# try.net
KiCad netlist of a schematic drawn in EAGLE
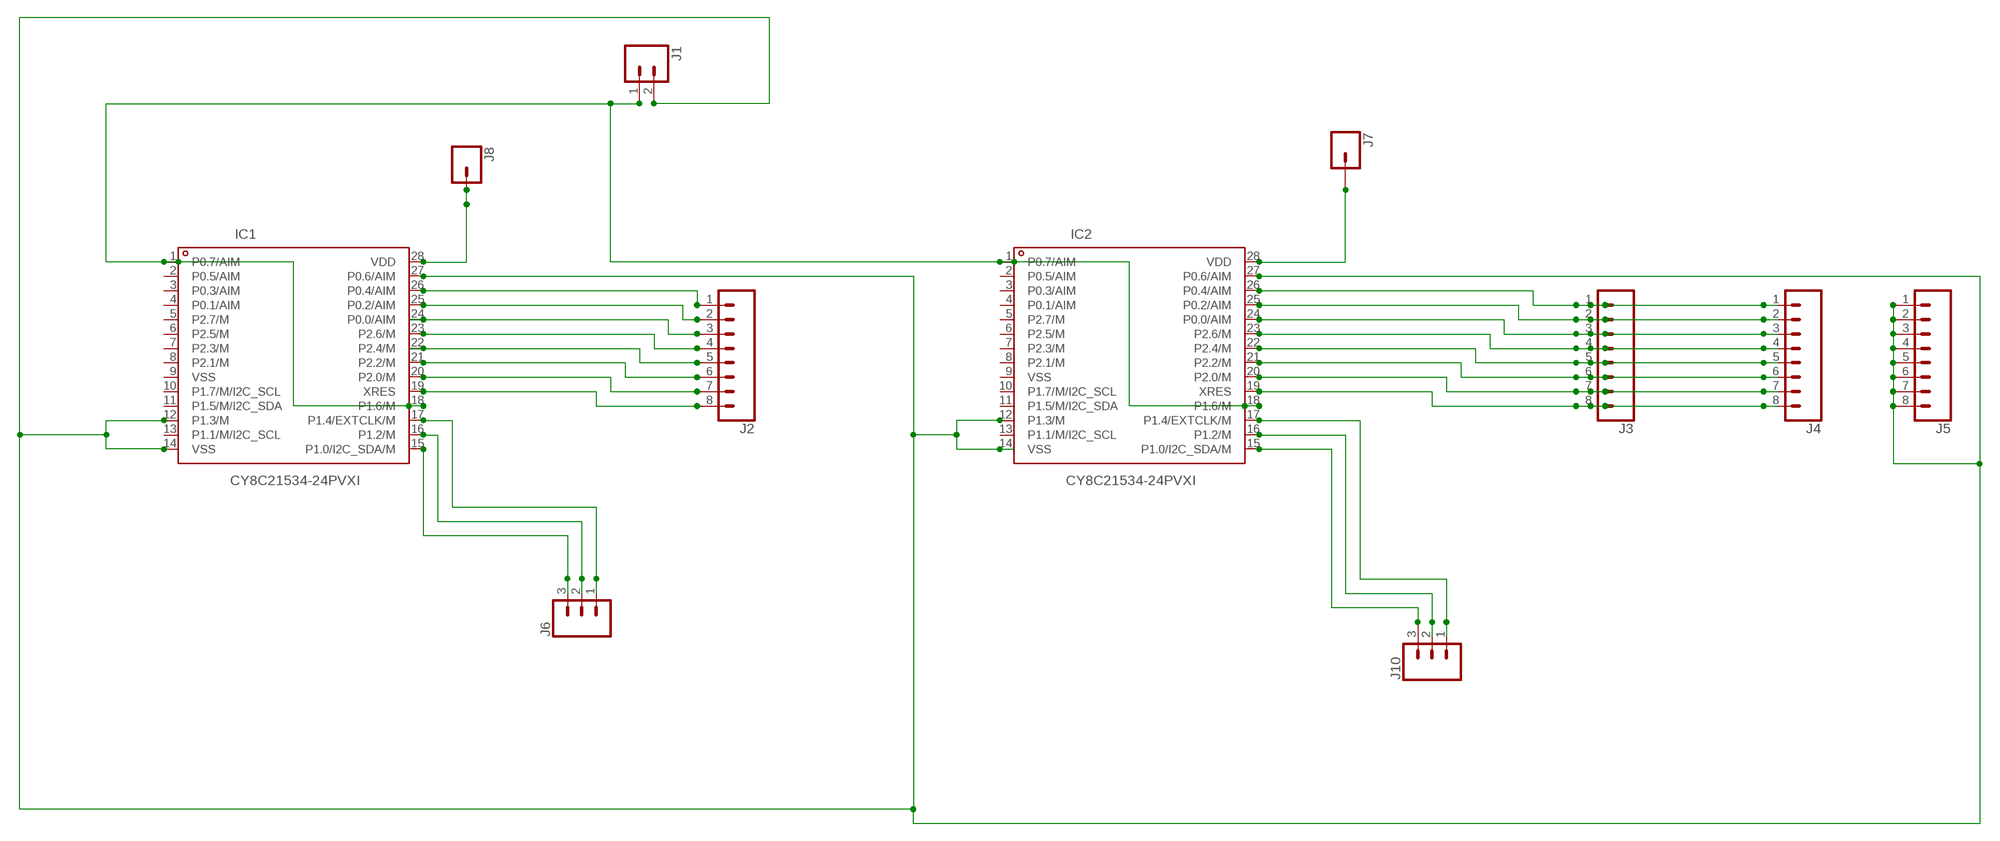
[diagram p0: schematic, sheet 1]

(export (version "E")
  (design (tool "Eeschema 10.0.6"))
  (components
    (comp (ref "IC1")
      (value "CY8C21534-24PVXI")
      (footprint "eagle-import:SSOP28")
      (libsource (lib "eagle-import") (part "CY8C21534-24PVXI"))
    )
    (comp (ref "IC2")
      (value "CY8C21534-24PVXI")
      (footprint "eagle-import:SSOP28")
      (libsource (lib "eagle-import") (part "CY8C21534-24PVXI"))
    )
    (comp (ref "J1")
      (value "CONN_02PTH3")
      (footprint "eagle-import:1X02_LONGPADS")
      (libsource (lib "eagle-import") (part "CONN_02PTH3"))
    )
    (comp (ref "J2")
      (value "CONN_08LONGPADS")
      (footprint "eagle-import:1X08_LONGPADS")
      (libsource (lib "eagle-import") (part "CONN_08LONGPADS"))
    )
    (comp (ref "J3")
      (value "CONN_08LONGPADS")
      (footprint "eagle-import:1X08_LONGPADS")
      (libsource (lib "eagle-import") (part "CONN_08LONGPADS"))
    )
    (comp (ref "J4")
      (value "CONN_08LONGPADS")
      (footprint "eagle-import:1X08_LONGPADS")
      (libsource (lib "eagle-import") (part "CONN_08LONGPADS"))
    )
    (comp (ref "J5")
      (value "CONN_08LONGPADS")
      (footprint "eagle-import:1X08_LONGPADS")
      (libsource (lib "eagle-import") (part "CONN_08LONGPADS"))
    )
    (comp (ref "J6")
      (value "CONN_03LONGPADS")
      (footprint "eagle-import:1X03_LONGPADS")
      (libsource (lib "eagle-import") (part "CONN_03LONGPADS"))
    )
    (comp (ref "J7")
      (value "CONN_01PTH_LONGPAD")
      (footprint "eagle-import:1X01_LONGPAD")
      (libsource (lib "eagle-import") (part "CONN_01PTH_LONGPAD"))
    )
    (comp (ref "J8")
      (value "CONN_01PTH_LONGPAD")
      (footprint "eagle-import:1X01_LONGPAD")
      (libsource (lib "eagle-import") (part "CONN_01PTH_LONGPAD"))
    )
    (comp (ref "J10")
      (value "CONN_03LONGPADS")
      (footprint "eagle-import:1X03_LONGPADS")
      (libsource (lib "eagle-import") (part "CONN_03LONGPADS"))
    )
  )
  (nets
    (net (code "1") (name "Net-(IC1-P0.0{slash}AIM)") (class "Default")
      (node (ref "IC1") (pin "24") (pinfunction "P0.0/AIM_24") (pintype "bidirectional"))
      (node (ref "J2") (pin "3") (pinfunction "3_3") (pintype "passive"))
    )
    (net (code "2") (name "Net-(IC1-P0.2{slash}AIM)") (class "Default")
      (node (ref "IC1") (pin "25") (pinfunction "P0.2/AIM_25") (pintype "bidirectional"))
      (node (ref "J2") (pin "2") (pinfunction "2_2") (pintype "passive"))
    )
    (net (code "3") (name "Net-(IC1-P0.4{slash}AIM)") (class "Default")
      (node (ref "IC1") (pin "26") (pinfunction "P0.4/AIM_26") (pintype "bidirectional"))
      (node (ref "J2") (pin "1") (pinfunction "1_1") (pintype "passive"))
    )
    (net (code "4") (name "Net-(IC1-P0.6{slash}AIM)") (class "Default")
      (node (ref "IC1") (pin "12") (pinfunction "P1.3/M_12") (pintype "bidirectional"))
      (node (ref "IC1") (pin "14") (pinfunction "VSS_14") (pintype "bidirectional"))
      (node (ref "IC1") (pin "27") (pinfunction "P0.6/AIM_27") (pintype "bidirectional"))
      (node (ref "IC2") (pin "12") (pinfunction "P1.3/M_12") (pintype "bidirectional"))
      (node (ref "IC2") (pin "14") (pinfunction "VSS_14") (pintype "bidirectional"))
      (node (ref "IC2") (pin "27") (pinfunction "P0.6/AIM_27") (pintype "bidirectional"))
      (node (ref "J1") (pin "2") (pinfunction "2_2") (pintype "passive"))
      (node (ref "J5") (pin "1") (pinfunction "1_1") (pintype "passive"))
      (node (ref "J5") (pin "2") (pinfunction "2_2") (pintype "passive"))
      (node (ref "J5") (pin "3") (pinfunction "3_3") (pintype "passive"))
      (node (ref "J5") (pin "4") (pinfunction "4_4") (pintype "passive"))
      (node (ref "J5") (pin "5") (pinfunction "5_5") (pintype "passive"))
      (node (ref "J5") (pin "6") (pinfunction "6_6") (pintype "passive"))
      (node (ref "J5") (pin "7") (pinfunction "7_7") (pintype "passive"))
      (node (ref "J5") (pin "8") (pinfunction "8_8") (pintype "passive"))
    )
    (net (code "5") (name "Net-(IC1-P0.7{slash}AIM)") (class "Default")
      (node (ref "IC1") (pin "1") (pinfunction "P0.7/AIM_1") (pintype "bidirectional"))
      (node (ref "IC1") (pin "18") (pinfunction "P1.6/M_18") (pintype "bidirectional"))
      (node (ref "IC2") (pin "1") (pinfunction "P0.7/AIM_1") (pintype "bidirectional"))
      (node (ref "IC2") (pin "18") (pinfunction "P1.6/M_18") (pintype "bidirectional"))
      (node (ref "J1") (pin "1") (pinfunction "1_1") (pintype "passive"))
    )
    (net (code "6") (name "Net-(IC1-P1.0{slash}I2C_SDA{slash}M)") (class "Default")
      (node (ref "IC1") (pin "15") (pinfunction "P1.0/I2C_SDA/M_15") (pintype "bidirectional"))
      (node (ref "J6") (pin "3") (pinfunction "3_3") (pintype "passive"))
    )
    (net (code "7") (name "Net-(IC1-P1.2{slash}M)") (class "Default")
      (node (ref "IC1") (pin "16") (pinfunction "P1.2/M_16") (pintype "bidirectional"))
      (node (ref "J6") (pin "2") (pinfunction "2_2") (pintype "passive"))
    )
    (net (code "8") (name "Net-(IC1-P1.4{slash}EXTCLK{slash}M)") (class "Default")
      (node (ref "IC1") (pin "17") (pinfunction "P1.4/EXTCLK/M_17") (pintype "bidirectional"))
      (node (ref "J6") (pin "1") (pinfunction "1_1") (pintype "passive"))
    )
    (net (code "9") (name "Net-(IC1-P2.0{slash}M)") (class "Default")
      (node (ref "IC1") (pin "20") (pinfunction "P2.0/M_20") (pintype "bidirectional"))
      (node (ref "J2") (pin "7") (pinfunction "7_7") (pintype "passive"))
    )
    (net (code "10") (name "Net-(IC1-P2.2{slash}M)") (class "Default")
      (node (ref "IC1") (pin "21") (pinfunction "P2.2/M_21") (pintype "bidirectional"))
      (node (ref "J2") (pin "6") (pinfunction "6_6") (pintype "passive"))
    )
    (net (code "11") (name "Net-(IC1-P2.4{slash}M)") (class "Default")
      (node (ref "IC1") (pin "22") (pinfunction "P2.4/M_22") (pintype "bidirectional"))
      (node (ref "J2") (pin "5") (pinfunction "5_5") (pintype "passive"))
    )
    (net (code "12") (name "Net-(IC1-P2.6{slash}M)") (class "Default")
      (node (ref "IC1") (pin "23") (pinfunction "P2.6/M_23") (pintype "bidirectional"))
      (node (ref "J2") (pin "4") (pinfunction "4_4") (pintype "passive"))
    )
    (net (code "13") (name "Net-(IC1-VDD)") (class "Default")
      (node (ref "IC1") (pin "28") (pinfunction "VDD_28") (pintype "bidirectional"))
      (node (ref "J8") (pin "1") (pinfunction "1_1") (pintype "passive"))
    )
    (net (code "14") (name "Net-(IC1-XRES)") (class "Default")
      (node (ref "IC1") (pin "19") (pinfunction "XRES_19") (pintype "bidirectional"))
      (node (ref "J2") (pin "8") (pinfunction "8_8") (pintype "passive"))
    )
    (net (code "15") (name "Net-(IC2-P0.0{slash}AIM)") (class "Default")
      (node (ref "IC2") (pin "24") (pinfunction "P0.0/AIM_24") (pintype "bidirectional"))
      (node (ref "J3") (pin "3") (pinfunction "3_3") (pintype "passive"))
      (node (ref "J4") (pin "3") (pinfunction "3_3") (pintype "passive"))
    )
    (net (code "16") (name "Net-(IC2-P0.2{slash}AIM)") (class "Default")
      (node (ref "IC2") (pin "25") (pinfunction "P0.2/AIM_25") (pintype "bidirectional"))
      (node (ref "J3") (pin "2") (pinfunction "2_2") (pintype "passive"))
      (node (ref "J4") (pin "2") (pinfunction "2_2") (pintype "passive"))
    )
    (net (code "17") (name "Net-(IC2-P0.4{slash}AIM)") (class "Default")
      (node (ref "IC2") (pin "26") (pinfunction "P0.4/AIM_26") (pintype "bidirectional"))
      (node (ref "J3") (pin "1") (pinfunction "1_1") (pintype "passive"))
      (node (ref "J4") (pin "1") (pinfunction "1_1") (pintype "passive"))
    )
    (net (code "18") (name "Net-(IC2-P1.0{slash}I2C_SDA{slash}M)") (class "Default")
      (node (ref "IC2") (pin "15") (pinfunction "P1.0/I2C_SDA/M_15") (pintype "bidirectional"))
      (node (ref "J10") (pin "3") (pinfunction "3_3") (pintype "passive"))
    )
    (net (code "19") (name "Net-(IC2-P1.2{slash}M)") (class "Default")
      (node (ref "IC2") (pin "16") (pinfunction "P1.2/M_16") (pintype "bidirectional"))
      (node (ref "J10") (pin "2") (pinfunction "2_2") (pintype "passive"))
    )
    (net (code "20") (name "Net-(IC2-P1.4{slash}EXTCLK{slash}M)") (class "Default")
      (node (ref "IC2") (pin "17") (pinfunction "P1.4/EXTCLK/M_17") (pintype "bidirectional"))
      (node (ref "J10") (pin "1") (pinfunction "1_1") (pintype "passive"))
    )
    (net (code "21") (name "Net-(IC2-P2.0{slash}M)") (class "Default")
      (node (ref "IC2") (pin "20") (pinfunction "P2.0/M_20") (pintype "bidirectional"))
      (node (ref "J3") (pin "7") (pinfunction "7_7") (pintype "passive"))
      (node (ref "J4") (pin "7") (pinfunction "7_7") (pintype "passive"))
    )
    (net (code "22") (name "Net-(IC2-P2.2{slash}M)") (class "Default")
      (node (ref "IC2") (pin "21") (pinfunction "P2.2/M_21") (pintype "bidirectional"))
      (node (ref "J3") (pin "6") (pinfunction "6_6") (pintype "passive"))
      (node (ref "J4") (pin "6") (pinfunction "6_6") (pintype "passive"))
    )
    (net (code "23") (name "Net-(IC2-P2.4{slash}M)") (class "Default")
      (node (ref "IC2") (pin "22") (pinfunction "P2.4/M_22") (pintype "bidirectional"))
      (node (ref "J3") (pin "5") (pinfunction "5_5") (pintype "passive"))
      (node (ref "J4") (pin "5") (pinfunction "5_5") (pintype "passive"))
    )
    (net (code "24") (name "Net-(IC2-P2.6{slash}M)") (class "Default")
      (node (ref "IC2") (pin "23") (pinfunction "P2.6/M_23") (pintype "bidirectional"))
      (node (ref "J3") (pin "4") (pinfunction "4_4") (pintype "passive"))
      (node (ref "J4") (pin "4") (pinfunction "4_4") (pintype "passive"))
    )
    (net (code "25") (name "Net-(IC2-VDD)") (class "Default")
      (node (ref "IC2") (pin "28") (pinfunction "VDD_28") (pintype "bidirectional"))
      (node (ref "J7") (pin "1") (pinfunction "1_1") (pintype "passive"))
    )
    (net (code "26") (name "Net-(IC2-XRES)") (class "Default")
      (node (ref "IC2") (pin "19") (pinfunction "XRES_19") (pintype "bidirectional"))
      (node (ref "J3") (pin "8") (pinfunction "8_8") (pintype "passive"))
      (node (ref "J4") (pin "8") (pinfunction "8_8") (pintype "passive"))
    )
    (net (code "27") (name "unconnected-(IC1-P0.1{slash}AIM-Pad4)") (class "Default")
      (node (ref "IC1") (pin "4") (pinfunction "P0.1/AIM_4") (pintype "bidirectional"))
    )
    (net (code "28") (name "unconnected-(IC1-P0.3{slash}AIM-Pad3)") (class "Default")
      (node (ref "IC1") (pin "3") (pinfunction "P0.3/AIM_3") (pintype "bidirectional"))
    )
    (net (code "29") (name "unconnected-(IC1-P0.5{slash}AIM-Pad2)") (class "Default")
      (node (ref "IC1") (pin "2") (pinfunction "P0.5/AIM_2") (pintype "bidirectional"))
    )
    (net (code "30") (name "unconnected-(IC1-P1.1{slash}M{slash}I2C_SCL-Pad13)") (class "Default")
      (node (ref "IC1") (pin "13") (pinfunction "P1.1/M/I2C_SCL_13") (pintype "bidirectional"))
    )
    (net (code "31") (name "unconnected-(IC1-P1.5{slash}M{slash}I2C_SDA-Pad11)") (class "Default")
      (node (ref "IC1") (pin "11") (pinfunction "P1.5/M/I2C_SDA_11") (pintype "bidirectional"))
    )
    (net (code "32") (name "unconnected-(IC1-P1.7{slash}M{slash}I2C_SCL-Pad10)") (class "Default")
      (node (ref "IC1") (pin "10") (pinfunction "P1.7/M/I2C_SCL_10") (pintype "bidirectional"))
    )
    (net (code "33") (name "unconnected-(IC1-P2.1{slash}M-Pad8)") (class "Default")
      (node (ref "IC1") (pin "8") (pinfunction "P2.1/M_8") (pintype "bidirectional"))
    )
    (net (code "34") (name "unconnected-(IC1-P2.3{slash}M-Pad7)") (class "Default")
      (node (ref "IC1") (pin "7") (pinfunction "P2.3/M_7") (pintype "bidirectional"))
    )
    (net (code "35") (name "unconnected-(IC1-P2.5{slash}M-Pad6)") (class "Default")
      (node (ref "IC1") (pin "6") (pinfunction "P2.5/M_6") (pintype "bidirectional"))
    )
    (net (code "36") (name "unconnected-(IC1-P2.7{slash}M-Pad5)") (class "Default")
      (node (ref "IC1") (pin "5") (pinfunction "P2.7/M_5") (pintype "bidirectional"))
    )
    (net (code "37") (name "unconnected-(IC1-VSS-Pad9)") (class "Default")
      (node (ref "IC1") (pin "9") (pinfunction "VSS_9") (pintype "bidirectional"))
    )
    (net (code "38") (name "unconnected-(IC2-P0.1{slash}AIM-Pad4)") (class "Default")
      (node (ref "IC2") (pin "4") (pinfunction "P0.1/AIM_4") (pintype "bidirectional"))
    )
    (net (code "39") (name "unconnected-(IC2-P0.3{slash}AIM-Pad3)") (class "Default")
      (node (ref "IC2") (pin "3") (pinfunction "P0.3/AIM_3") (pintype "bidirectional"))
    )
    (net (code "40") (name "unconnected-(IC2-P0.5{slash}AIM-Pad2)") (class "Default")
      (node (ref "IC2") (pin "2") (pinfunction "P0.5/AIM_2") (pintype "bidirectional"))
    )
    (net (code "41") (name "unconnected-(IC2-P1.1{slash}M{slash}I2C_SCL-Pad13)") (class "Default")
      (node (ref "IC2") (pin "13") (pinfunction "P1.1/M/I2C_SCL_13") (pintype "bidirectional"))
    )
    (net (code "42") (name "unconnected-(IC2-P1.5{slash}M{slash}I2C_SDA-Pad11)") (class "Default")
      (node (ref "IC2") (pin "11") (pinfunction "P1.5/M/I2C_SDA_11") (pintype "bidirectional"))
    )
    (net (code "43") (name "unconnected-(IC2-P1.7{slash}M{slash}I2C_SCL-Pad10)") (class "Default")
      (node (ref "IC2") (pin "10") (pinfunction "P1.7/M/I2C_SCL_10") (pintype "bidirectional"))
    )
    (net (code "44") (name "unconnected-(IC2-P2.1{slash}M-Pad8)") (class "Default")
      (node (ref "IC2") (pin "8") (pinfunction "P2.1/M_8") (pintype "bidirectional"))
    )
    (net (code "45") (name "unconnected-(IC2-P2.3{slash}M-Pad7)") (class "Default")
      (node (ref "IC2") (pin "7") (pinfunction "P2.3/M_7") (pintype "bidirectional"))
    )
    (net (code "46") (name "unconnected-(IC2-P2.5{slash}M-Pad6)") (class "Default")
      (node (ref "IC2") (pin "6") (pinfunction "P2.5/M_6") (pintype "bidirectional"))
    )
    (net (code "47") (name "unconnected-(IC2-P2.7{slash}M-Pad5)") (class "Default")
      (node (ref "IC2") (pin "5") (pinfunction "P2.7/M_5") (pintype "bidirectional"))
    )
    (net (code "48") (name "unconnected-(IC2-VSS-Pad9)") (class "Default")
      (node (ref "IC2") (pin "9") (pinfunction "VSS_9") (pintype "bidirectional"))
    )
  )
)
